# Main_Board_-_Copy.net
KiCad netlist of a schematic drawn in Altium Designer
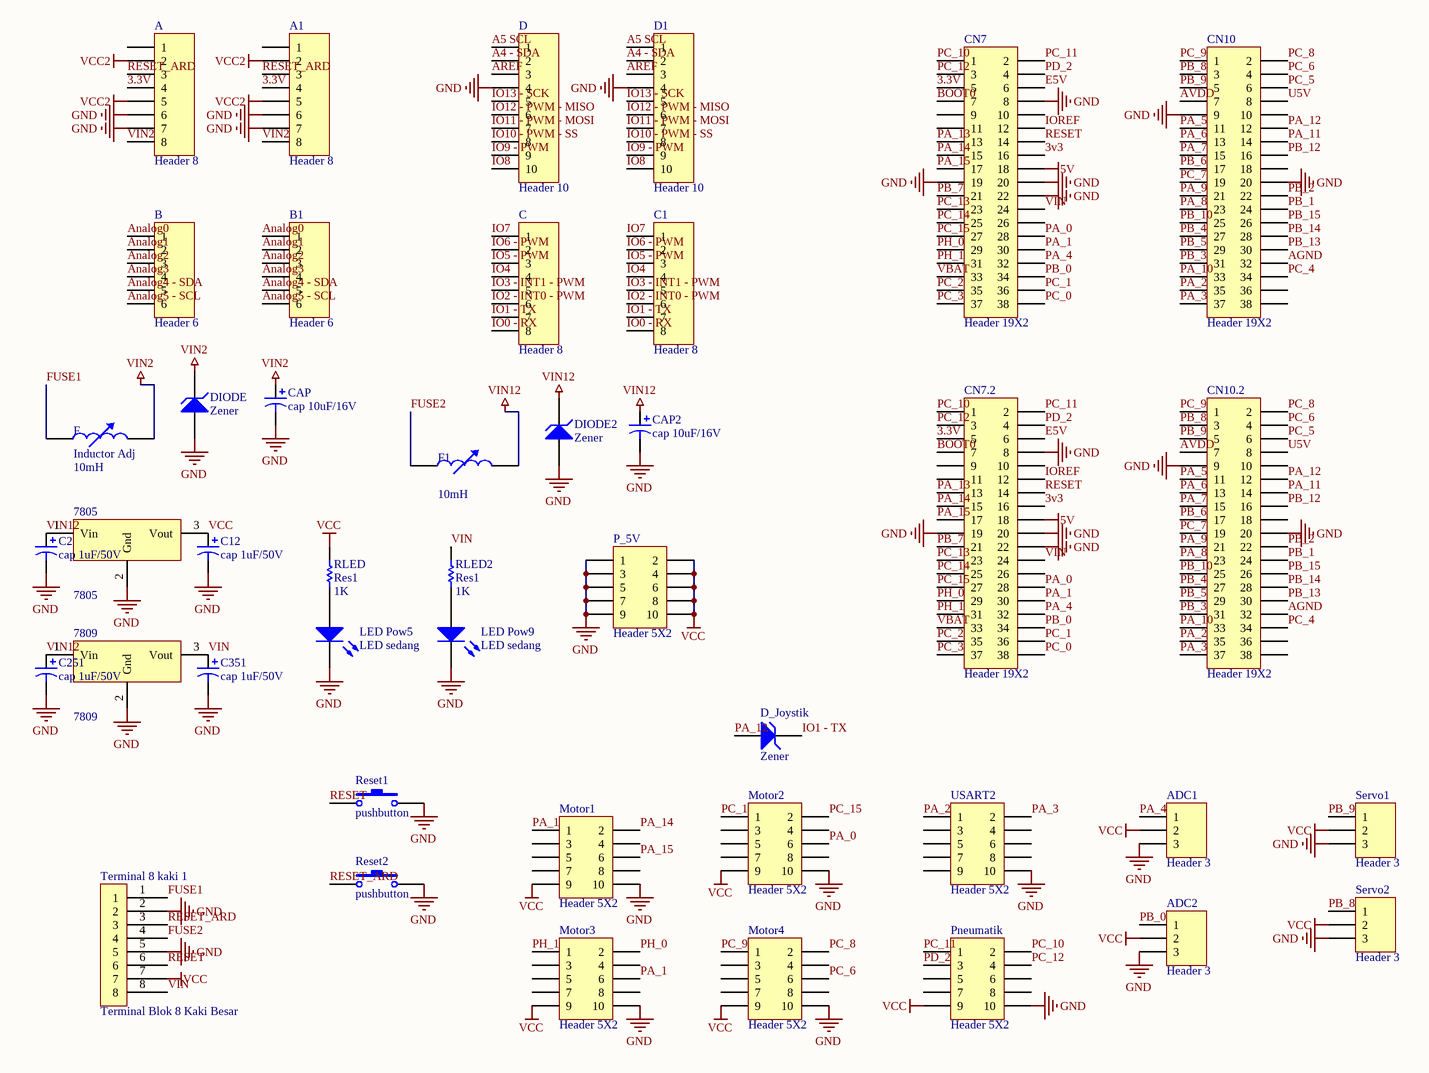
[diagram p0: Main Board - Copy.SchDoc]

(export (version "E")
  (design (tool "Eeschema 10.0.6"))
  (components
    (comp (ref "7805")
      (value "7805")
      (footprint "78XX/79XX")
      (libsource (lib "agfa other components") (part "7805/7809/7812/7905/7909/7912"))
    )
    (comp (ref "7809")
      (value "7809")
      (footprint "78XX/79XX")
      (libsource (lib "agfa other components") (part "7805/7809/7812/7905/7909/7912"))
    )
    (comp (ref "A")
      (value "Header 8")
      (footprint "HDR1X8")
      (description "Header, 8-Pin")
      (fields (field (name "PUBLISHER") "Altium Limited"))
      (libsource (lib "Miscellaneous Connectors") (part "Header 8"))
    )
    (comp (ref "A1")
      (value "Header 8")
      (footprint "HDR1X8")
      (description "Header, 8-Pin")
      (fields (field (name "PUBLISHER") "Altium Limited"))
      (libsource (lib "Miscellaneous Connectors") (part "Header 8"))
    )
    (comp (ref "ADC1")
      (value "Header 3")
      (footprint "HDR1X3")
      (description "Header, 3-Pin")
      (fields (field (name "PUBLISHER") "Altium Limited"))
      (libsource (lib "Miscellaneous Connectors") (part "Header 3"))
    )
    (comp (ref "ADC2")
      (value "Header 3")
      (footprint "HDR1X3")
      (description "Header, 3-Pin")
      (fields (field (name "PUBLISHER") "Altium Limited"))
      (libsource (lib "Miscellaneous Connectors") (part "Header 3"))
    )
    (comp (ref "B")
      (value "Header 6")
      (footprint "HDR1X6")
      (description "Header, 6-Pin")
      (fields (field (name "PUBLISHER") "Altium Limited"))
      (libsource (lib "Miscellaneous Connectors") (part "Header 6"))
    )
    (comp (ref "B1")
      (value "Header 6")
      (footprint "HDR1X6")
      (description "Header, 6-Pin")
      (fields (field (name "PUBLISHER") "Altium Limited"))
      (libsource (lib "Miscellaneous Connectors") (part "Header 6"))
    )
    (comp (ref "C")
      (value "Header 8")
      (footprint "HDR1X8")
      (description "Header, 8-Pin")
      (fields (field (name "PUBLISHER") "Altium Limited"))
      (libsource (lib "Miscellaneous Connectors") (part "Header 8"))
    )
    (comp (ref "C1")
      (value "Header 8")
      (footprint "HDR1X8")
      (description "Header, 8-Pin")
      (fields (field (name "PUBLISHER") "Altium Limited"))
      (libsource (lib "Miscellaneous Connectors") (part "Header 8"))
    )
    (comp (ref "C2")
      (value "cap 1uF/50V")
      (footprint "cap 1uF/50V")
      (libsource (lib "agfa other components") (part "cap 1uF/50V"))
    )
    (comp (ref "C12")
      (value "cap 1uF/50V")
      (footprint "cap 1uF/50V")
      (libsource (lib "agfa other components") (part "cap 1uF/50V"))
    )
    (comp (ref "C251")
      (value "cap 1uF/50V")
      (footprint "cap 1uF/50V")
      (libsource (lib "agfa other components") (part "cap 1uF/50V"))
    )
    (comp (ref "C351")
      (value "cap 1uF/50V")
      (footprint "cap 1uF/50V")
      (libsource (lib "agfa other components") (part "cap 1uF/50V"))
    )
    (comp (ref "CAP")
      (value "cap 10uF/16V")
      (footprint "cap 10uF/16V")
      (libsource (lib "agfa other components") (part "cap 10uF/16V"))
    )
    (comp (ref "CAP2")
      (value "cap 10uF/16V")
      (footprint "cap 10uF/16V")
      (libsource (lib "agfa other components") (part "cap 10uF/16V"))
    )
    (comp (ref "CN7")
      (value "Header 19X2")
      (footprint "HDR2X19")
      (description "Header, 19-Pin, Dual row")
      (fields (field (name "PUBLISHER") "Altium Limited"))
      (libsource (lib "Miscellaneous Connectors") (part "Header 19X2"))
    )
    (comp (ref "CN7.2")
      (value "Header 19X2")
      (footprint "HDR2X19")
      (description "Header, 19-Pin, Dual row")
      (fields (field (name "PUBLISHER") "Altium Limited"))
      (libsource (lib "Miscellaneous Connectors") (part "Header 19X2"))
    )
    (comp (ref "CN10")
      (value "Header 19X2")
      (footprint "HDR2X19")
      (description "Header, 19-Pin, Dual row")
      (fields (field (name "PUBLISHER") "Altium Limited"))
      (libsource (lib "Miscellaneous Connectors") (part "Header 19X2"))
    )
    (comp (ref "CN10.2")
      (value "Header 19X2")
      (footprint "HDR2X19")
      (description "Header, 19-Pin, Dual row")
      (fields (field (name "PUBLISHER") "Altium Limited"))
      (libsource (lib "Miscellaneous Connectors") (part "Header 19X2"))
    )
    (comp (ref "D")
      (value "Header 10")
      (footprint "HDR1X10")
      (description "Header, 10-Pin")
      (fields (field (name "PUBLISHER") "Altium Limited"))
      (libsource (lib "Miscellaneous Connectors") (part "Header 10"))
    )
    (comp (ref "D1")
      (value "Header 10")
      (footprint "HDR1X10")
      (description "Header, 10-Pin")
      (fields (field (name "PUBLISHER") "Altium Limited"))
      (libsource (lib "Miscellaneous Connectors") (part "Header 10"))
    )
    (comp (ref "DIODE")
      (value "Zener")
      (footprint "D Zener")
      (libsource (lib "agfa other components") (part "D Zener"))
    )
    (comp (ref "DIODE2")
      (value "Zener")
      (footprint "D Zener")
      (libsource (lib "agfa other components") (part "D Zener"))
    )
    (comp (ref "D_Joystik")
      (value "Zener")
      (footprint "D Zener")
      (libsource (lib "agfa other components") (part "D Zener"))
    )
    (comp (ref "F")
      (value "Inductor Adj")
      (footprint "AXIAL-0.8")
      (description "Adjustable Inductor")
      (fields (field (name "ALTIUM_VALUE") "10mH") (field (name "PUBLISHER") "Altium Limited"))
      (libsource (lib "Miscellaneous Devices") (part "Inductor Adj"))
    )
    (comp (ref "F1")
      (value "10mH")
      (footprint "AXIAL-0.8")
      (description "Adjustable Inductor")
      (fields (field (name "Comment") "Inductor Adj") (field (name "PUBLISHER") "Altium Limited"))
      (libsource (lib "Miscellaneous Devices") (part "Inductor Adj"))
    )
    (comp (ref "LED Pow5")
      (value "LED sedang")
      (footprint "LED sedang")
      (libsource (lib "agfa other components") (part "LED sedang"))
    )
    (comp (ref "LED Pow9")
      (value "LED sedang")
      (footprint "LED sedang")
      (libsource (lib "agfa other components") (part "LED sedang"))
    )
    (comp (ref "Motor1")
      (value "Header 5X2")
      (footprint "HDR2X5")
      (description "Header, 5-Pin, Dual row")
      (fields (field (name "PUBLISHER") "Altium Limited"))
      (libsource (lib "Miscellaneous Connectors") (part "Header 5X2"))
    )
    (comp (ref "Motor2")
      (value "Header 5X2")
      (footprint "HDR2X5")
      (description "Header, 5-Pin, Dual row")
      (fields (field (name "PUBLISHER") "Altium Limited"))
      (libsource (lib "Miscellaneous Connectors") (part "Header 5X2"))
    )
    (comp (ref "Motor3")
      (value "Header 5X2")
      (footprint "HDR2X5")
      (description "Header, 5-Pin, Dual row")
      (fields (field (name "PUBLISHER") "Altium Limited"))
      (libsource (lib "Miscellaneous Connectors") (part "Header 5X2"))
    )
    (comp (ref "Motor4")
      (value "Header 5X2")
      (footprint "HDR2X5")
      (description "Header, 5-Pin, Dual row")
      (fields (field (name "PUBLISHER") "Altium Limited"))
      (libsource (lib "Miscellaneous Connectors") (part "Header 5X2"))
    )
    (comp (ref "Pneumatik")
      (value "Header 5X2")
      (footprint "HDR2X5")
      (description "Header, 5-Pin, Dual row")
      (fields (field (name "PUBLISHER") "Altium Limited"))
      (libsource (lib "Miscellaneous Connectors") (part "Header 5X2"))
    )
    (comp (ref "P_5V")
      (value "Header 5X2")
      (footprint "HDR2X5")
      (description "Header, 5-Pin, Dual row")
      (fields (field (name "PUBLISHER") "Altium Limited"))
      (libsource (lib "Miscellaneous Connectors") (part "Header 5X2"))
    )
    (comp (ref "Reset1")
      (value "pushbutton")
      (footprint "pushbutton")
      (libsource (lib "agfa other components") (part "pushbutton"))
    )
    (comp (ref "Reset2")
      (value "pushbutton")
      (footprint "pushbutton")
      (libsource (lib "agfa other components") (part "pushbutton"))
    )
    (comp (ref "RLED")
      (value "Res1")
      (footprint "AXIAL-0.3")
      (description "Resistor")
      (fields (field (name "ALTIUM_VALUE") "1K") (field (name "PUBLISHER") "Altium Limited"))
      (libsource (lib "Miscellaneous Devices") (part "Res1"))
    )
    (comp (ref "RLED2")
      (value "Res1")
      (footprint "AXIAL-0.3")
      (description "Resistor")
      (fields (field (name "ALTIUM_VALUE") "1K") (field (name "PUBLISHER") "Altium Limited"))
      (libsource (lib "Miscellaneous Devices") (part "Res1"))
    )
    (comp (ref "Servo1")
      (value "Header 3")
      (footprint "HDR1X3")
      (description "Header, 3-Pin")
      (fields (field (name "PUBLISHER") "Altium Limited"))
      (libsource (lib "Miscellaneous Connectors") (part "Header 3"))
    )
    (comp (ref "Servo2")
      (value "Header 3")
      (footprint "HDR1X3")
      (description "Header, 3-Pin")
      (fields (field (name "PUBLISHER") "Altium Limited"))
      (libsource (lib "Miscellaneous Connectors") (part "Header 3"))
    )
    (comp (ref "Terminal 8 kaki 1")
      (value "Terminal Blok 8 Kaki Besar")
      (footprint "TERMINAL 8 KAKI")
      (libsource (lib "Library Ausiher") (part "Terminal Block 8 kaki"))
    )
    (comp (ref "USART2")
      (value "Header 5X2")
      (footprint "HDR2X5")
      (description "Header, 5-Pin, Dual row")
      (fields (field (name "PUBLISHER") "Altium Limited"))
      (libsource (lib "Miscellaneous Connectors") (part "Header 5X2"))
    )
  )
  (nets
    (net (code "1") (name "/3.3V") (class "Default")
      (node (ref "A") (pin "4") (pinfunction "4_4") (pintype "passive"))
      (node (ref "A1") (pin "4") (pinfunction "4_4") (pintype "passive"))
      (node (ref "CN7") (pin "5") (pinfunction "5_5") (pintype "passive"))
      (node (ref "CN7.2") (pin "5") (pinfunction "5_5") (pintype "passive"))
    )
    (net (code "2") (name "/3v3") (class "Default")
      (node (ref "CN7") (pin "16") (pinfunction "16_16") (pintype "passive"))
      (node (ref "CN7.2") (pin "16") (pinfunction "16_16") (pintype "passive"))
    )
    (net (code "3") (name "/A4 - SDA") (class "Default")
      (node (ref "D") (pin "2") (pinfunction "2_2") (pintype "passive"))
      (node (ref "D1") (pin "2") (pinfunction "2_2") (pintype "passive"))
    )
    (net (code "4") (name "/A5 SCL") (class "Default")
      (node (ref "D") (pin "1") (pinfunction "1_1") (pintype "passive"))
      (node (ref "D1") (pin "1") (pinfunction "1_1") (pintype "passive"))
    )
    (net (code "5") (name "/AGND") (class "Default")
      (node (ref "CN10") (pin "32") (pinfunction "32_32") (pintype "passive"))
      (node (ref "CN10.2") (pin "32") (pinfunction "32_32") (pintype "passive"))
    )
    (net (code "6") (name "/AREF") (class "Default")
      (node (ref "D") (pin "3") (pinfunction "3_3") (pintype "passive"))
      (node (ref "D1") (pin "3") (pinfunction "3_3") (pintype "passive"))
    )
    (net (code "7") (name "/AVDD") (class "Default")
      (node (ref "CN10") (pin "7") (pinfunction "7_7") (pintype "passive"))
      (node (ref "CN10.2") (pin "7") (pinfunction "7_7") (pintype "passive"))
    )
    (net (code "8") (name "/Analog0") (class "Default")
      (node (ref "B") (pin "1") (pinfunction "1_1") (pintype "passive"))
      (node (ref "B1") (pin "1") (pinfunction "1_1") (pintype "passive"))
    )
    (net (code "9") (name "/Analog1") (class "Default")
      (node (ref "B") (pin "2") (pinfunction "2_2") (pintype "passive"))
      (node (ref "B1") (pin "2") (pinfunction "2_2") (pintype "passive"))
    )
    (net (code "10") (name "/Analog2") (class "Default")
      (node (ref "B") (pin "3") (pinfunction "3_3") (pintype "passive"))
      (node (ref "B1") (pin "3") (pinfunction "3_3") (pintype "passive"))
    )
    (net (code "11") (name "/Analog3") (class "Default")
      (node (ref "B") (pin "4") (pinfunction "4_4") (pintype "passive"))
      (node (ref "B1") (pin "4") (pinfunction "4_4") (pintype "passive"))
    )
    (net (code "12") (name "/Analog4 - SDA") (class "Default")
      (node (ref "B") (pin "5") (pinfunction "5_5") (pintype "passive"))
      (node (ref "B1") (pin "5") (pinfunction "5_5") (pintype "passive"))
    )
    (net (code "13") (name "/Analog5 - SCL") (class "Default")
      (node (ref "B") (pin "6") (pinfunction "6_6") (pintype "passive"))
      (node (ref "B1") (pin "6") (pinfunction "6_6") (pintype "passive"))
    )
    (net (code "14") (name "/BOOT0") (class "Default")
      (node (ref "CN7") (pin "7") (pinfunction "7_7") (pintype "passive"))
      (node (ref "CN7.2") (pin "7") (pinfunction "7_7") (pintype "passive"))
    )
    (net (code "15") (name "/E5V") (class "Default")
      (node (ref "CN7") (pin "6") (pinfunction "6_6") (pintype "passive"))
      (node (ref "CN7.2") (pin "6") (pinfunction "6_6") (pintype "passive"))
    )
    (net (code "16") (name "/FUSE1") (class "Default")
      (node (ref "F") (pin "1") (pinfunction "1_1") (pintype "passive"))
      (node (ref "Terminal 8 kaki 1") (pin "1") (pinfunction "1_1") (pintype "passive"))
    )
    (net (code "17") (name "/FUSE2") (class "Default")
      (node (ref "F1") (pin "1") (pinfunction "1_1") (pintype "passive"))
      (node (ref "Terminal 8 kaki 1") (pin "4") (pinfunction "4_4") (pintype "passive"))
    )
    (net (code "18") (name "/IO0 - RX") (class "Default")
      (node (ref "C") (pin "8") (pinfunction "8_8") (pintype "passive"))
      (node (ref "C1") (pin "8") (pinfunction "8_8") (pintype "passive"))
    )
    (net (code "19") (name "/IO1 - TX") (class "Default")
      (node (ref "C") (pin "7") (pinfunction "7_7") (pintype "passive"))
      (node (ref "C1") (pin "7") (pinfunction "7_7") (pintype "passive"))
      (node (ref "D_Joystik") (pin "2") (pinfunction "K_2") (pintype "passive"))
    )
    (net (code "20") (name "/IO2 - INT0 - PWM") (class "Default")
      (node (ref "C") (pin "6") (pinfunction "6_6") (pintype "passive"))
      (node (ref "C1") (pin "6") (pinfunction "6_6") (pintype "passive"))
    )
    (net (code "21") (name "/IO3 - INT1 - PWM") (class "Default")
      (node (ref "C") (pin "5") (pinfunction "5_5") (pintype "passive"))
      (node (ref "C1") (pin "5") (pinfunction "5_5") (pintype "passive"))
    )
    (net (code "22") (name "/IO4") (class "Default")
      (node (ref "C") (pin "4") (pinfunction "4_4") (pintype "passive"))
      (node (ref "C1") (pin "4") (pinfunction "4_4") (pintype "passive"))
    )
    (net (code "23") (name "/IO5 - PWM") (class "Default")
      (node (ref "C") (pin "3") (pinfunction "3_3") (pintype "passive"))
      (node (ref "C1") (pin "3") (pinfunction "3_3") (pintype "passive"))
    )
    (net (code "24") (name "/IO6 - PWM") (class "Default")
      (node (ref "C") (pin "2") (pinfunction "2_2") (pintype "passive"))
      (node (ref "C1") (pin "2") (pinfunction "2_2") (pintype "passive"))
    )
    (net (code "25") (name "/IO7") (class "Default")
      (node (ref "C") (pin "1") (pinfunction "1_1") (pintype "passive"))
      (node (ref "C1") (pin "1") (pinfunction "1_1") (pintype "passive"))
    )
    (net (code "26") (name "/IO8") (class "Default")
      (node (ref "D") (pin "10") (pinfunction "10_10") (pintype "passive"))
      (node (ref "D1") (pin "10") (pinfunction "10_10") (pintype "passive"))
    )
    (net (code "27") (name "/IO9 - PWM") (class "Default")
      (node (ref "D") (pin "9") (pinfunction "9_9") (pintype "passive"))
      (node (ref "D1") (pin "9") (pinfunction "9_9") (pintype "passive"))
    )
    (net (code "28") (name "/IO10 - PWM - SS") (class "Default")
      (node (ref "D") (pin "8") (pinfunction "8_8") (pintype "passive"))
      (node (ref "D1") (pin "8") (pinfunction "8_8") (pintype "passive"))
    )
    (net (code "29") (name "/IO11 - PWM - MOSI") (class "Default")
      (node (ref "D") (pin "7") (pinfunction "7_7") (pintype "passive"))
      (node (ref "D1") (pin "7") (pinfunction "7_7") (pintype "passive"))
    )
    (net (code "30") (name "/IO12 - PWM - MISO") (class "Default")
      (node (ref "D") (pin "6") (pinfunction "6_6") (pintype "passive"))
      (node (ref "D1") (pin "6") (pinfunction "6_6") (pintype "passive"))
    )
    (net (code "31") (name "/IO13 - SCK") (class "Default")
      (node (ref "D") (pin "5") (pinfunction "5_5") (pintype "passive"))
      (node (ref "D1") (pin "5") (pinfunction "5_5") (pintype "passive"))
    )
    (net (code "32") (name "/IOREF") (class "Default")
      (node (ref "CN7") (pin "12") (pinfunction "12_12") (pintype "passive"))
      (node (ref "CN7.2") (pin "12") (pinfunction "12_12") (pintype "passive"))
    )
    (net (code "33") (name "/PA_0") (class "Default")
      (node (ref "CN7") (pin "28") (pinfunction "28_28") (pintype "passive"))
      (node (ref "CN7.2") (pin "28") (pinfunction "28_28") (pintype "passive"))
      (node (ref "Motor2") (pin "6") (pinfunction "6_6") (pintype "passive"))
    )
    (net (code "34") (name "/PA_1") (class "Default")
      (node (ref "CN7") (pin "30") (pinfunction "30_30") (pintype "passive"))
      (node (ref "CN7.2") (pin "30") (pinfunction "30_30") (pintype "passive"))
      (node (ref "Motor3") (pin "6") (pinfunction "6_6") (pintype "passive"))
    )
    (net (code "35") (name "/PA_2") (class "Default")
      (node (ref "CN10") (pin "35") (pinfunction "35_35") (pintype "passive"))
      (node (ref "CN10.2") (pin "35") (pinfunction "35_35") (pintype "passive"))
      (node (ref "USART2") (pin "1") (pinfunction "1_1") (pintype "passive"))
    )
    (net (code "36") (name "/PA_3") (class "Default")
      (node (ref "CN10") (pin "37") (pinfunction "37_37") (pintype "passive"))
      (node (ref "CN10.2") (pin "37") (pinfunction "37_37") (pintype "passive"))
      (node (ref "USART2") (pin "2") (pinfunction "2_2") (pintype "passive"))
    )
    (net (code "37") (name "/PA_4") (class "Default")
      (node (ref "ADC1") (pin "1") (pinfunction "1_1") (pintype "passive"))
      (node (ref "CN7") (pin "32") (pinfunction "32_32") (pintype "passive"))
      (node (ref "CN7.2") (pin "32") (pinfunction "32_32") (pintype "passive"))
    )
    (net (code "38") (name "/PA_5") (class "Default")
      (node (ref "CN10") (pin "11") (pinfunction "11_11") (pintype "passive"))
      (node (ref "CN10.2") (pin "11") (pinfunction "11_11") (pintype "passive"))
    )
    (net (code "39") (name "/PA_6") (class "Default")
      (node (ref "CN10") (pin "13") (pinfunction "13_13") (pintype "passive"))
      (node (ref "CN10.2") (pin "13") (pinfunction "13_13") (pintype "passive"))
    )
    (net (code "40") (name "/PA_7") (class "Default")
      (node (ref "CN10") (pin "15") (pinfunction "15_15") (pintype "passive"))
      (node (ref "CN10.2") (pin "15") (pinfunction "15_15") (pintype "passive"))
    )
    (net (code "41") (name "/PA_8") (class "Default")
      (node (ref "CN10") (pin "23") (pinfunction "23_23") (pintype "passive"))
      (node (ref "CN10.2") (pin "23") (pinfunction "23_23") (pintype "passive"))
    )
    (net (code "42") (name "/PA_9") (class "Default")
      (node (ref "CN10") (pin "21") (pinfunction "21_21") (pintype "passive"))
      (node (ref "CN10.2") (pin "21") (pinfunction "21_21") (pintype "passive"))
    )
    (net (code "43") (name "/PA_10") (class "Default")
      (node (ref "CN10") (pin "33") (pinfunction "33_33") (pintype "passive"))
      (node (ref "CN10.2") (pin "33") (pinfunction "33_33") (pintype "passive"))
    )
    (net (code "44") (name "/PA_11") (class "Default")
      (node (ref "CN10") (pin "14") (pinfunction "14_14") (pintype "passive"))
      (node (ref "CN10.2") (pin "14") (pinfunction "14_14") (pintype "passive"))
    )
    (net (code "45") (name "/PA_12") (class "Default")
      (node (ref "CN10") (pin "12") (pinfunction "12_12") (pintype "passive"))
      (node (ref "CN10.2") (pin "12") (pinfunction "12_12") (pintype "passive"))
      (node (ref "D_Joystik") (pin "1") (pinfunction "A_1") (pintype "passive"))
    )
    (net (code "46") (name "/PA_13") (class "Default")
      (node (ref "CN7") (pin "13") (pinfunction "13_13") (pintype "passive"))
      (node (ref "CN7.2") (pin "13") (pinfunction "13_13") (pintype "passive"))
      (node (ref "Motor1") (pin "1") (pinfunction "1_1") (pintype "passive"))
    )
    (net (code "47") (name "/PA_14") (class "Default")
      (node (ref "CN7") (pin "15") (pinfunction "15_15") (pintype "passive"))
      (node (ref "CN7.2") (pin "15") (pinfunction "15_15") (pintype "passive"))
      (node (ref "Motor1") (pin "2") (pinfunction "2_2") (pintype "passive"))
    )
    (net (code "48") (name "/PA_15") (class "Default")
      (node (ref "CN7") (pin "17") (pinfunction "17_17") (pintype "passive"))
      (node (ref "CN7.2") (pin "17") (pinfunction "17_17") (pintype "passive"))
      (node (ref "Motor1") (pin "6") (pinfunction "6_6") (pintype "passive"))
    )
    (net (code "49") (name "/PB_0") (class "Default")
      (node (ref "ADC2") (pin "1") (pinfunction "1_1") (pintype "passive"))
      (node (ref "CN7") (pin "34") (pinfunction "34_34") (pintype "passive"))
      (node (ref "CN7.2") (pin "34") (pinfunction "34_34") (pintype "passive"))
    )
    (net (code "50") (name "/PB_1") (class "Default")
      (node (ref "CN10") (pin "24") (pinfunction "24_24") (pintype "passive"))
      (node (ref "CN10.2") (pin "24") (pinfunction "24_24") (pintype "passive"))
    )
    (net (code "51") (name "/PB_2") (class "Default")
      (node (ref "CN10") (pin "22") (pinfunction "22_22") (pintype "passive"))
      (node (ref "CN10.2") (pin "22") (pinfunction "22_22") (pintype "passive"))
    )
    (net (code "52") (name "/PB_3") (class "Default")
      (node (ref "CN10") (pin "31") (pinfunction "31_31") (pintype "passive"))
      (node (ref "CN10.2") (pin "31") (pinfunction "31_31") (pintype "passive"))
    )
    (net (code "53") (name "/PB_4") (class "Default")
      (node (ref "CN10") (pin "27") (pinfunction "27_27") (pintype "passive"))
      (node (ref "CN10.2") (pin "27") (pinfunction "27_27") (pintype "passive"))
    )
    (net (code "54") (name "/PB_5") (class "Default")
      (node (ref "CN10") (pin "29") (pinfunction "29_29") (pintype "passive"))
      (node (ref "CN10.2") (pin "29") (pinfunction "29_29") (pintype "passive"))
    )
    (net (code "55") (name "/PB_6") (class "Default")
      (node (ref "CN10") (pin "17") (pinfunction "17_17") (pintype "passive"))
      (node (ref "CN10.2") (pin "17") (pinfunction "17_17") (pintype "passive"))
    )
    (net (code "56") (name "/PB_7") (class "Default")
      (node (ref "CN7") (pin "21") (pinfunction "21_21") (pintype "passive"))
      (node (ref "CN7.2") (pin "21") (pinfunction "21_21") (pintype "passive"))
    )
    (net (code "57") (name "/PB_8") (class "Default")
      (node (ref "CN10") (pin "3") (pinfunction "3_3") (pintype "passive"))
      (node (ref "CN10.2") (pin "3") (pinfunction "3_3") (pintype "passive"))
      (node (ref "Servo2") (pin "1") (pinfunction "1_1") (pintype "passive"))
    )
    (net (code "58") (name "/PB_9") (class "Default")
      (node (ref "CN10") (pin "5") (pinfunction "5_5") (pintype "passive"))
      (node (ref "CN10.2") (pin "5") (pinfunction "5_5") (pintype "passive"))
      (node (ref "Servo1") (pin "1") (pinfunction "1_1") (pintype "passive"))
    )
    (net (code "59") (name "/PB_10") (class "Default")
      (node (ref "CN10") (pin "25") (pinfunction "25_25") (pintype "passive"))
      (node (ref "CN10.2") (pin "25") (pinfunction "25_25") (pintype "passive"))
    )
    (net (code "60") (name "/PB_12") (class "Default")
      (node (ref "CN10") (pin "16") (pinfunction "16_16") (pintype "passive"))
      (node (ref "CN10.2") (pin "16") (pinfunction "16_16") (pintype "passive"))
    )
    (net (code "61") (name "/PB_13") (class "Default")
      (node (ref "CN10") (pin "30") (pinfunction "30_30") (pintype "passive"))
      (node (ref "CN10.2") (pin "30") (pinfunction "30_30") (pintype "passive"))
    )
    (net (code "62") (name "/PB_14") (class "Default")
      (node (ref "CN10") (pin "28") (pinfunction "28_28") (pintype "passive"))
      (node (ref "CN10.2") (pin "28") (pinfunction "28_28") (pintype "passive"))
    )
    (net (code "63") (name "/PB_15") (class "Default")
      (node (ref "CN10") (pin "26") (pinfunction "26_26") (pintype "passive"))
      (node (ref "CN10.2") (pin "26") (pinfunction "26_26") (pintype "passive"))
    )
    (net (code "64") (name "/PC_0") (class "Default")
      (node (ref "CN7") (pin "38") (pinfunction "38_38") (pintype "passive"))
      (node (ref "CN7.2") (pin "38") (pinfunction "38_38") (pintype "passive"))
    )
    (net (code "65") (name "/PC_1") (class "Default")
      (node (ref "CN7") (pin "36") (pinfunction "36_36") (pintype "passive"))
      (node (ref "CN7.2") (pin "36") (pinfunction "36_36") (pintype "passive"))
    )
    (net (code "66") (name "/PC_2") (class "Default")
      (node (ref "CN7") (pin "35") (pinfunction "35_35") (pintype "passive"))
      (node (ref "CN7.2") (pin "35") (pinfunction "35_35") (pintype "passive"))
    )
    (net (code "67") (name "/PC_3") (class "Default")
      (node (ref "CN7") (pin "37") (pinfunction "37_37") (pintype "passive"))
      (node (ref "CN7.2") (pin "37") (pinfunction "37_37") (pintype "passive"))
    )
    (net (code "68") (name "/PC_4") (class "Default")
      (node (ref "CN10") (pin "34") (pinfunction "34_34") (pintype "passive"))
      (node (ref "CN10.2") (pin "34") (pinfunction "34_34") (pintype "passive"))
    )
    (net (code "69") (name "/PC_5") (class "Default")
      (node (ref "CN10") (pin "6") (pinfunction "6_6") (pintype "passive"))
      (node (ref "CN10.2") (pin "6") (pinfunction "6_6") (pintype "passive"))
    )
    (net (code "70") (name "/PC_6") (class "Default")
      (node (ref "CN10") (pin "4") (pinfunction "4_4") (pintype "passive"))
      (node (ref "CN10.2") (pin "4") (pinfunction "4_4") (pintype "passive"))
      (node (ref "Motor4") (pin "6") (pinfunction "6_6") (pintype "passive"))
    )
    (net (code "71") (name "/PC_7") (class "Default")
      (node (ref "CN10") (pin "19") (pinfunction "19_19") (pintype "passive"))
      (node (ref "CN10.2") (pin "19") (pinfunction "19_19") (pintype "passive"))
    )
    (net (code "72") (name "/PC_8") (class "Default")
      (node (ref "CN10") (pin "2") (pinfunction "2_2") (pintype "passive"))
      (node (ref "CN10.2") (pin "2") (pinfunction "2_2") (pintype "passive"))
      (node (ref "Motor4") (pin "2") (pinfunction "2_2") (pintype "passive"))
    )
    (net (code "73") (name "/PC_9") (class "Default")
      (node (ref "CN10") (pin "1") (pinfunction "1_1") (pintype "passive"))
      (node (ref "CN10.2") (pin "1") (pinfunction "1_1") (pintype "passive"))
      (node (ref "Motor4") (pin "1") (pinfunction "1_1") (pintype "passive"))
    )
    (net (code "74") (name "/PC_10") (class "Default")
      (node (ref "CN7") (pin "1") (pinfunction "1_1") (pintype "passive"))
      (node (ref "CN7.2") (pin "1") (pinfunction "1_1") (pintype "passive"))
      (node (ref "Pneumatik") (pin "2") (pinfunction "2_2") (pintype "passive"))
    )
    (net (code "75") (name "/PC_11") (class "Default")
      (node (ref "CN7") (pin "2") (pinfunction "2_2") (pintype "passive"))
      (node (ref "CN7.2") (pin "2") (pinfunction "2_2") (pintype "passive"))
      (node (ref "Pneumatik") (pin "1") (pinfunction "1_1") (pintype "passive"))
    )
    (net (code "76") (name "/PC_12") (class "Default")
      (node (ref "CN7") (pin "3") (pinfunction "3_3") (pintype "passive"))
      (node (ref "CN7.2") (pin "3") (pinfunction "3_3") (pintype "passive"))
      (node (ref "Pneumatik") (pin "4") (pinfunction "4_4") (pintype "passive"))
    )
    (net (code "77") (name "/PC_13") (class "Default")
      (node (ref "CN7") (pin "23") (pinfunction "23_23") (pintype "passive"))
      (node (ref "CN7.2") (pin "23") (pinfunction "23_23") (pintype "passive"))
    )
    (net (code "78") (name "/PC_14") (class "Default")
      (node (ref "CN7") (pin "25") (pinfunction "25_25") (pintype "passive"))
      (node (ref "CN7.2") (pin "25") (pinfunction "25_25") (pintype "passive"))
      (node (ref "Motor2") (pin "1") (pinfunction "1_1") (pintype "passive"))
    )
    (net (code "79") (name "/PC_15") (class "Default")
      (node (ref "CN7") (pin "27") (pinfunction "27_27") (pintype "passive"))
      (node (ref "CN7.2") (pin "27") (pinfunction "27_27") (pintype "passive"))
      (node (ref "Motor2") (pin "2") (pinfunction "2_2") (pintype "passive"))
    )
    (net (code "80") (name "/PD_2") (class "Default")
      (node (ref "CN7") (pin "4") (pinfunction "4_4") (pintype "passive"))
      (node (ref "CN7.2") (pin "4") (pinfunction "4_4") (pintype "passive"))
      (node (ref "Pneumatik") (pin "3") (pinfunction "3_3") (pintype "passive"))
    )
    (net (code "81") (name "/PH_0") (class "Default")
      (node (ref "CN7") (pin "29") (pinfunction "29_29") (pintype "passive"))
      (node (ref "CN7.2") (pin "29") (pinfunction "29_29") (pintype "passive"))
      (node (ref "Motor3") (pin "2") (pinfunction "2_2") (pintype "passive"))
    )
    (net (code "82") (name "/PH_1") (class "Default")
      (node (ref "CN7") (pin "31") (pinfunction "31_31") (pintype "passive"))
      (node (ref "CN7.2") (pin "31") (pinfunction "31_31") (pintype "passive"))
      (node (ref "Motor3") (pin "1") (pinfunction "1_1") (pintype "passive"))
    )
    (net (code "83") (name "/RESET") (class "Default")
      (node (ref "CN7") (pin "14") (pinfunction "14_14") (pintype "passive"))
      (node (ref "CN7.2") (pin "14") (pinfunction "14_14") (pintype "passive"))
      (node (ref "Reset1") (pin "1") (pinfunction "1_1") (pintype "passive"))
      (node (ref "Terminal 8 kaki 1") (pin "6") (pinfunction "6_6") (pintype "passive"))
    )
    (net (code "84") (name "/RESET_ARD") (class "Default")
      (node (ref "A") (pin "3") (pinfunction "3_3") (pintype "passive"))
      (node (ref "A1") (pin "3") (pinfunction "3_3") (pintype "passive"))
      (node (ref "Reset2") (pin "1") (pinfunction "1_1") (pintype "passive"))
      (node (ref "Terminal 8 kaki 1") (pin "3") (pinfunction "3_3") (pintype "passive"))
    )
    (net (code "85") (name "/U5V") (class "Default")
      (node (ref "CN10") (pin "8") (pinfunction "8_8") (pintype "passive"))
      (node (ref "CN10.2") (pin "8") (pinfunction "8_8") (pintype "passive"))
    )
    (net (code "86") (name "/VBAT") (class "Default")
      (node (ref "CN7") (pin "33") (pinfunction "33_33") (pintype "passive"))
      (node (ref "CN7.2") (pin "33") (pinfunction "33_33") (pintype "passive"))
    )
    (net (code "87") (name "/VIN") (class "Default")
      (node (ref "7809") (pin "3") (pinfunction "Vout_3") (pintype "passive"))
      (node (ref "C351") (pin "1") (pinfunction "1_1") (pintype "passive"))
      (node (ref "CN7") (pin "24") (pinfunction "24_24") (pintype "passive"))
      (node (ref "CN7.2") (pin "24") (pinfunction "24_24") (pintype "passive"))
      (node (ref "RLED2") (pin "2") (pinfunction "2_2") (pintype "passive"))
      (node (ref "Terminal 8 kaki 1") (pin "8") (pinfunction "8_8") (pintype "passive"))
    )
    (net (code "88") (name "5V") (class "Default")
      (node (ref "CN7") (pin "18") (pinfunction "18_18") (pintype "passive"))
      (node (ref "CN7.2") (pin "18") (pinfunction "18_18") (pintype "passive"))
    )
    (net (code "89") (name "GND") (class "Default")
      (node (ref "7805") (pin "2") (pinfunction "Gnd_2") (pintype "passive"))
      (node (ref "7809") (pin "2") (pinfunction "Gnd_2") (pintype "passive"))
      (node (ref "A") (pin "6") (pinfunction "6_6") (pintype "passive"))
      (node (ref "A") (pin "7") (pinfunction "7_7") (pintype "passive"))
      (node (ref "A1") (pin "6") (pinfunction "6_6") (pintype "passive"))
      (node (ref "A1") (pin "7") (pinfunction "7_7") (pintype "passive"))
      (node (ref "ADC1") (pin "3") (pinfunction "3_3") (pintype "passive"))
      (node (ref "ADC2") (pin "3") (pinfunction "3_3") (pintype "passive"))
      (node (ref "C12") (pin "2") (pinfunction "2_2") (pintype "passive"))
      (node (ref "C2") (pin "2") (pinfunction "2_2") (pintype "passive"))
      (node (ref "C251") (pin "2") (pinfunction "2_2") (pintype "passive"))
      (node (ref "C351") (pin "2") (pinfunction "2_2") (pintype "passive"))
      (node (ref "CAP") (pin "2") (pinfunction "2_2") (pintype "passive"))
      (node (ref "CAP2") (pin "2") (pinfunction "2_2") (pintype "passive"))
      (node (ref "CN10") (pin "20") (pinfunction "20_20") (pintype "passive"))
      (node (ref "CN10") (pin "9") (pinfunction "9_9") (pintype "passive"))
      (node (ref "CN10.2") (pin "20") (pinfunction "20_20") (pintype "passive"))
      (node (ref "CN10.2") (pin "9") (pinfunction "9_9") (pintype "passive"))
      (node (ref "CN7") (pin "19") (pinfunction "19_19") (pintype "passive"))
      (node (ref "CN7") (pin "20") (pinfunction "20_20") (pintype "passive"))
      (node (ref "CN7") (pin "22") (pinfunction "22_22") (pintype "passive"))
      (node (ref "CN7") (pin "8") (pinfunction "8_8") (pintype "passive"))
      (node (ref "CN7.2") (pin "19") (pinfunction "19_19") (pintype "passive"))
      (node (ref "CN7.2") (pin "20") (pinfunction "20_20") (pintype "passive"))
      (node (ref "CN7.2") (pin "22") (pinfunction "22_22") (pintype "passive"))
      (node (ref "CN7.2") (pin "8") (pinfunction "8_8") (pintype "passive"))
      (node (ref "D") (pin "4") (pinfunction "4_4") (pintype "passive"))
      (node (ref "D1") (pin "4") (pinfunction "4_4") (pintype "passive"))
      (node (ref "DIODE") (pin "1") (pinfunction "A_1") (pintype "passive"))
      (node (ref "DIODE2") (pin "1") (pinfunction "A_1") (pintype "passive"))
      (node (ref "LED Pow5") (pin "2") (pinfunction "K_2") (pintype "passive"))
      (node (ref "LED Pow9") (pin "2") (pinfunction "K_2") (pintype "passive"))
      (node (ref "Motor1") (pin "10") (pinfunction "10_10") (pintype "passive"))
      (node (ref "Motor2") (pin "10") (pinfunction "10_10") (pintype "passive"))
      (node (ref "Motor3") (pin "10") (pinfunction "10_10") (pintype "passive"))
      (node (ref "Motor4") (pin "10") (pinfunction "10_10") (pintype "passive"))
      (node (ref "P_5V") (pin "1") (pinfunction "1_1") (pintype "passive"))
      (node (ref "P_5V") (pin "3") (pinfunction "3_3") (pintype "passive"))
      (node (ref "P_5V") (pin "5") (pinfunction "5_5") (pintype "passive"))
      (node (ref "P_5V") (pin "7") (pinfunction "7_7") (pintype "passive"))
      (node (ref "P_5V") (pin "9") (pinfunction "9_9") (pintype "passive"))
      (node (ref "Pneumatik") (pin "10") (pinfunction "10_10") (pintype "passive"))
      (node (ref "Reset1") (pin "2") (pinfunction "2_2") (pintype "passive"))
      (node (ref "Reset2") (pin "2") (pinfunction "2_2") (pintype "passive"))
      (node (ref "Servo1") (pin "3") (pinfunction "3_3") (pintype "passive"))
      (node (ref "Servo2") (pin "3") (pinfunction "3_3") (pintype "passive"))
      (node (ref "Terminal 8 kaki 1") (pin "2") (pinfunction "2_2") (pintype "passive"))
      (node (ref "Terminal 8 kaki 1") (pin "5") (pinfunction "5_5") (pintype "passive"))
      (node (ref "USART2") (pin "10") (pinfunction "10_10") (pintype "passive"))
    )
    (net (code "90") (name "Net-(LED Pow5-A)") (class "Default")
      (node (ref "LED Pow5") (pin "1") (pinfunction "A_1") (pintype "passive"))
      (node (ref "RLED") (pin "1") (pinfunction "1_1") (pintype "passive"))
    )
    (net (code "91") (name "Net-(LED Pow9-A)") (class "Default")
      (node (ref "LED Pow9") (pin "1") (pinfunction "A_1") (pintype "passive"))
      (node (ref "RLED2") (pin "1") (pinfunction "1_1") (pintype "passive"))
    )
    (net (code "92") (name "VCC") (class "Default")
      (node (ref "7805") (pin "3") (pinfunction "Vout_3") (pintype "passive"))
      (node (ref "ADC1") (pin "2") (pinfunction "2_2") (pintype "passive"))
      (node (ref "ADC2") (pin "2") (pinfunction "2_2") (pintype "passive"))
      (node (ref "C12") (pin "1") (pinfunction "1_1") (pintype "passive"))
      (node (ref "Motor1") (pin "9") (pinfunction "9_9") (pintype "passive"))
      (node (ref "Motor2") (pin "9") (pinfunction "9_9") (pintype "passive"))
      (node (ref "Motor3") (pin "9") (pinfunction "9_9") (pintype "passive"))
      (node (ref "Motor4") (pin "9") (pinfunction "9_9") (pintype "passive"))
      (node (ref "P_5V") (pin "10") (pinfunction "10_10") (pintype "passive"))
      (node (ref "P_5V") (pin "2") (pinfunction "2_2") (pintype "passive"))
      (node (ref "P_5V") (pin "4") (pinfunction "4_4") (pintype "passive"))
      (node (ref "P_5V") (pin "6") (pinfunction "6_6") (pintype "passive"))
      (node (ref "P_5V") (pin "8") (pinfunction "8_8") (pintype "passive"))
      (node (ref "Pneumatik") (pin "9") (pinfunction "9_9") (pintype "passive"))
      (node (ref "RLED") (pin "2") (pinfunction "2_2") (pintype "passive"))
      (node (ref "Servo1") (pin "2") (pinfunction "2_2") (pintype "passive"))
      (node (ref "Servo2") (pin "2") (pinfunction "2_2") (pintype "passive"))
      (node (ref "Terminal 8 kaki 1") (pin "7") (pinfunction "7_7") (pintype "passive"))
    )
    (net (code "93") (name "VCC2") (class "Default")
      (node (ref "A") (pin "2") (pinfunction "2_2") (pintype "passive"))
      (node (ref "A") (pin "5") (pinfunction "5_5") (pintype "passive"))
      (node (ref "A1") (pin "2") (pinfunction "2_2") (pintype "passive"))
      (node (ref "A1") (pin "5") (pinfunction "5_5") (pintype "passive"))
    )
    (net (code "94") (name "VIN2") (class "Default")
      (node (ref "A") (pin "8") (pinfunction "8_8") (pintype "passive"))
      (node (ref "A1") (pin "8") (pinfunction "8_8") (pintype "passive"))
      (node (ref "CAP") (pin "1") (pinfunction "1_1") (pintype "passive"))
      (node (ref "DIODE") (pin "2") (pinfunction "K_2") (pintype "passive"))
      (node (ref "F") (pin "2") (pinfunction "2_2") (pintype "passive"))
    )
    (net (code "95") (name "VIN12") (class "Default")
      (node (ref "7805") (pin "1") (pinfunction "Vin_1") (pintype "passive"))
      (node (ref "7809") (pin "1") (pinfunction "Vin_1") (pintype "passive"))
      (node (ref "C2") (pin "1") (pinfunction "1_1") (pintype "passive"))
      (node (ref "C251") (pin "1") (pinfunction "1_1") (pintype "passive"))
      (node (ref "CAP2") (pin "1") (pinfunction "1_1") (pintype "passive"))
      (node (ref "DIODE2") (pin "2") (pinfunction "K_2") (pintype "passive"))
      (node (ref "F1") (pin "2") (pinfunction "2_2") (pintype "passive"))
    )
    (net (code "96") (name "unconnected-(A-Pad1)") (class "Default")
      (node (ref "A") (pin "1") (pinfunction "1_1") (pintype "passive"))
    )
    (net (code "97") (name "unconnected-(A1-Pad1)") (class "Default")
      (node (ref "A1") (pin "1") (pinfunction "1_1") (pintype "passive"))
    )
    (net (code "98") (name "unconnected-(CN7-Pad9)") (class "Default")
      (node (ref "CN7") (pin "9") (pinfunction "9_9") (pintype "passive"))
    )
    (net (code "99") (name "unconnected-(CN7-Pad10)") (class "Default")
      (node (ref "CN7") (pin "10") (pinfunction "10_10") (pintype "passive"))
    )
    (net (code "100") (name "unconnected-(CN7-Pad11)") (class "Default")
      (node (ref "CN7") (pin "11") (pinfunction "11_11") (pintype "passive"))
    )
    (net (code "101") (name "unconnected-(CN7-Pad26)") (class "Default")
      (node (ref "CN7") (pin "26") (pinfunction "26_26") (pintype "passive"))
    )
    (net (code "102") (name "unconnected-(CN7.2-Pad9)") (class "Default")
      (node (ref "CN7.2") (pin "9") (pinfunction "9_9") (pintype "passive"))
    )
    (net (code "103") (name "unconnected-(CN7.2-Pad10)") (class "Default")
      (node (ref "CN7.2") (pin "10") (pinfunction "10_10") (pintype "passive"))
    )
    (net (code "104") (name "unconnected-(CN7.2-Pad11)") (class "Default")
      (node (ref "CN7.2") (pin "11") (pinfunction "11_11") (pintype "passive"))
    )
    (net (code "105") (name "unconnected-(CN7.2-Pad26)") (class "Default")
      (node (ref "CN7.2") (pin "26") (pinfunction "26_26") (pintype "passive"))
    )
    (net (code "106") (name "unconnected-(CN10-Pad10)") (class "Default")
      (node (ref "CN10") (pin "10") (pinfunction "10_10") (pintype "passive"))
    )
    (net (code "107") (name "unconnected-(CN10-Pad18)") (class "Default")
      (node (ref "CN10") (pin "18") (pinfunction "18_18") (pintype "passive"))
    )
    (net (code "108") (name "unconnected-(CN10-Pad36)") (class "Default")
      (node (ref "CN10") (pin "36") (pinfunction "36_36") (pintype "passive"))
    )
    (net (code "109") (name "unconnected-(CN10-Pad38)") (class "Default")
      (node (ref "CN10") (pin "38") (pinfunction "38_38") (pintype "passive"))
    )
    (net (code "110") (name "unconnected-(CN10.2-Pad10)") (class "Default")
      (node (ref "CN10.2") (pin "10") (pinfunction "10_10") (pintype "passive"))
    )
    (net (code "111") (name "unconnected-(CN10.2-Pad18)") (class "Default")
      (node (ref "CN10.2") (pin "18") (pinfunction "18_18") (pintype "passive"))
    )
    (net (code "112") (name "unconnected-(CN10.2-Pad36)") (class "Default")
      (node (ref "CN10.2") (pin "36") (pinfunction "36_36") (pintype "passive"))
    )
    (net (code "113") (name "unconnected-(CN10.2-Pad38)") (class "Default")
      (node (ref "CN10.2") (pin "38") (pinfunction "38_38") (pintype "passive"))
    )
    (net (code "114") (name "unconnected-(Motor1-Pad3)") (class "Default")
      (node (ref "Motor1") (pin "3") (pinfunction "3_3") (pintype "passive"))
    )
    (net (code "115") (name "unconnected-(Motor1-Pad4)") (class "Default")
      (node (ref "Motor1") (pin "4") (pinfunction "4_4") (pintype "passive"))
    )
    (net (code "116") (name "unconnected-(Motor1-Pad5)") (class "Default")
      (node (ref "Motor1") (pin "5") (pinfunction "5_5") (pintype "passive"))
    )
    (net (code "117") (name "unconnected-(Motor1-Pad7)") (class "Default")
      (node (ref "Motor1") (pin "7") (pinfunction "7_7") (pintype "passive"))
    )
    (net (code "118") (name "unconnected-(Motor1-Pad8)") (class "Default")
      (node (ref "Motor1") (pin "8") (pinfunction "8_8") (pintype "passive"))
    )
    (net (code "119") (name "unconnected-(Motor2-Pad3)") (class "Default")
      (node (ref "Motor2") (pin "3") (pinfunction "3_3") (pintype "passive"))
    )
    (net (code "120") (name "unconnected-(Motor2-Pad4)") (class "Default")
      (node (ref "Motor2") (pin "4") (pinfunction "4_4") (pintype "passive"))
    )
    (net (code "121") (name "unconnected-(Motor2-Pad5)") (class "Default")
      (node (ref "Motor2") (pin "5") (pinfunction "5_5") (pintype "passive"))
    )
    (net (code "122") (name "unconnected-(Motor2-Pad7)") (class "Default")
      (node (ref "Motor2") (pin "7") (pinfunction "7_7") (pintype "passive"))
    )
    (net (code "123") (name "unconnected-(Motor2-Pad8)") (class "Default")
      (node (ref "Motor2") (pin "8") (pinfunction "8_8") (pintype "passive"))
    )
    (net (code "124") (name "unconnected-(Motor3-Pad3)") (class "Default")
      (node (ref "Motor3") (pin "3") (pinfunction "3_3") (pintype "passive"))
    )
    (net (code "125") (name "unconnected-(Motor3-Pad4)") (class "Default")
      (node (ref "Motor3") (pin "4") (pinfunction "4_4") (pintype "passive"))
    )
    (net (code "126") (name "unconnected-(Motor3-Pad5)") (class "Default")
      (node (ref "Motor3") (pin "5") (pinfunction "5_5") (pintype "passive"))
    )
    (net (code "127") (name "unconnected-(Motor3-Pad7)") (class "Default")
      (node (ref "Motor3") (pin "7") (pinfunction "7_7") (pintype "passive"))
    )
    (net (code "128") (name "unconnected-(Motor3-Pad8)") (class "Default")
      (node (ref "Motor3") (pin "8") (pinfunction "8_8") (pintype "passive"))
    )
    (net (code "129") (name "unconnected-(Motor4-Pad3)") (class "Default")
      (node (ref "Motor4") (pin "3") (pinfunction "3_3") (pintype "passive"))
    )
    (net (code "130") (name "unconnected-(Motor4-Pad4)") (class "Default")
      (node (ref "Motor4") (pin "4") (pinfunction "4_4") (pintype "passive"))
    )
    (net (code "131") (name "unconnected-(Motor4-Pad5)") (class "Default")
      (node (ref "Motor4") (pin "5") (pinfunction "5_5") (pintype "passive"))
    )
    (net (code "132") (name "unconnected-(Motor4-Pad7)") (class "Default")
      (node (ref "Motor4") (pin "7") (pinfunction "7_7") (pintype "passive"))
    )
    (net (code "133") (name "unconnected-(Motor4-Pad8)") (class "Default")
      (node (ref "Motor4") (pin "8") (pinfunction "8_8") (pintype "passive"))
    )
    (net (code "134") (name "unconnected-(Pneumatik-Pad5)") (class "Default")
      (node (ref "Pneumatik") (pin "5") (pinfunction "5_5") (pintype "passive"))
    )
    (net (code "135") (name "unconnected-(Pneumatik-Pad6)") (class "Default")
      (node (ref "Pneumatik") (pin "6") (pinfunction "6_6") (pintype "passive"))
    )
    (net (code "136") (name "unconnected-(Pneumatik-Pad7)") (class "Default")
      (node (ref "Pneumatik") (pin "7") (pinfunction "7_7") (pintype "passive"))
    )
    (net (code "137") (name "unconnected-(Pneumatik-Pad8)") (class "Default")
      (node (ref "Pneumatik") (pin "8") (pinfunction "8_8") (pintype "passive"))
    )
    (net (code "138") (name "unconnected-(USART2-Pad3)") (class "Default")
      (node (ref "USART2") (pin "3") (pinfunction "3_3") (pintype "passive"))
    )
    (net (code "139") (name "unconnected-(USART2-Pad4)") (class "Default")
      (node (ref "USART2") (pin "4") (pinfunction "4_4") (pintype "passive"))
    )
    (net (code "140") (name "unconnected-(USART2-Pad5)") (class "Default")
      (node (ref "USART2") (pin "5") (pinfunction "5_5") (pintype "passive"))
    )
    (net (code "141") (name "unconnected-(USART2-Pad6)") (class "Default")
      (node (ref "USART2") (pin "6") (pinfunction "6_6") (pintype "passive"))
    )
    (net (code "142") (name "unconnected-(USART2-Pad7)") (class "Default")
      (node (ref "USART2") (pin "7") (pinfunction "7_7") (pintype "passive"))
    )
    (net (code "143") (name "unconnected-(USART2-Pad8)") (class "Default")
      (node (ref "USART2") (pin "8") (pinfunction "8_8") (pintype "passive"))
    )
    (net (code "144") (name "unconnected-(USART2-Pad9)") (class "Default")
      (node (ref "USART2") (pin "9") (pinfunction "9_9") (pintype "passive"))
    )
  )
)
